# Mixer.net
KiCad netlist of a schematic drawn in EAGLE
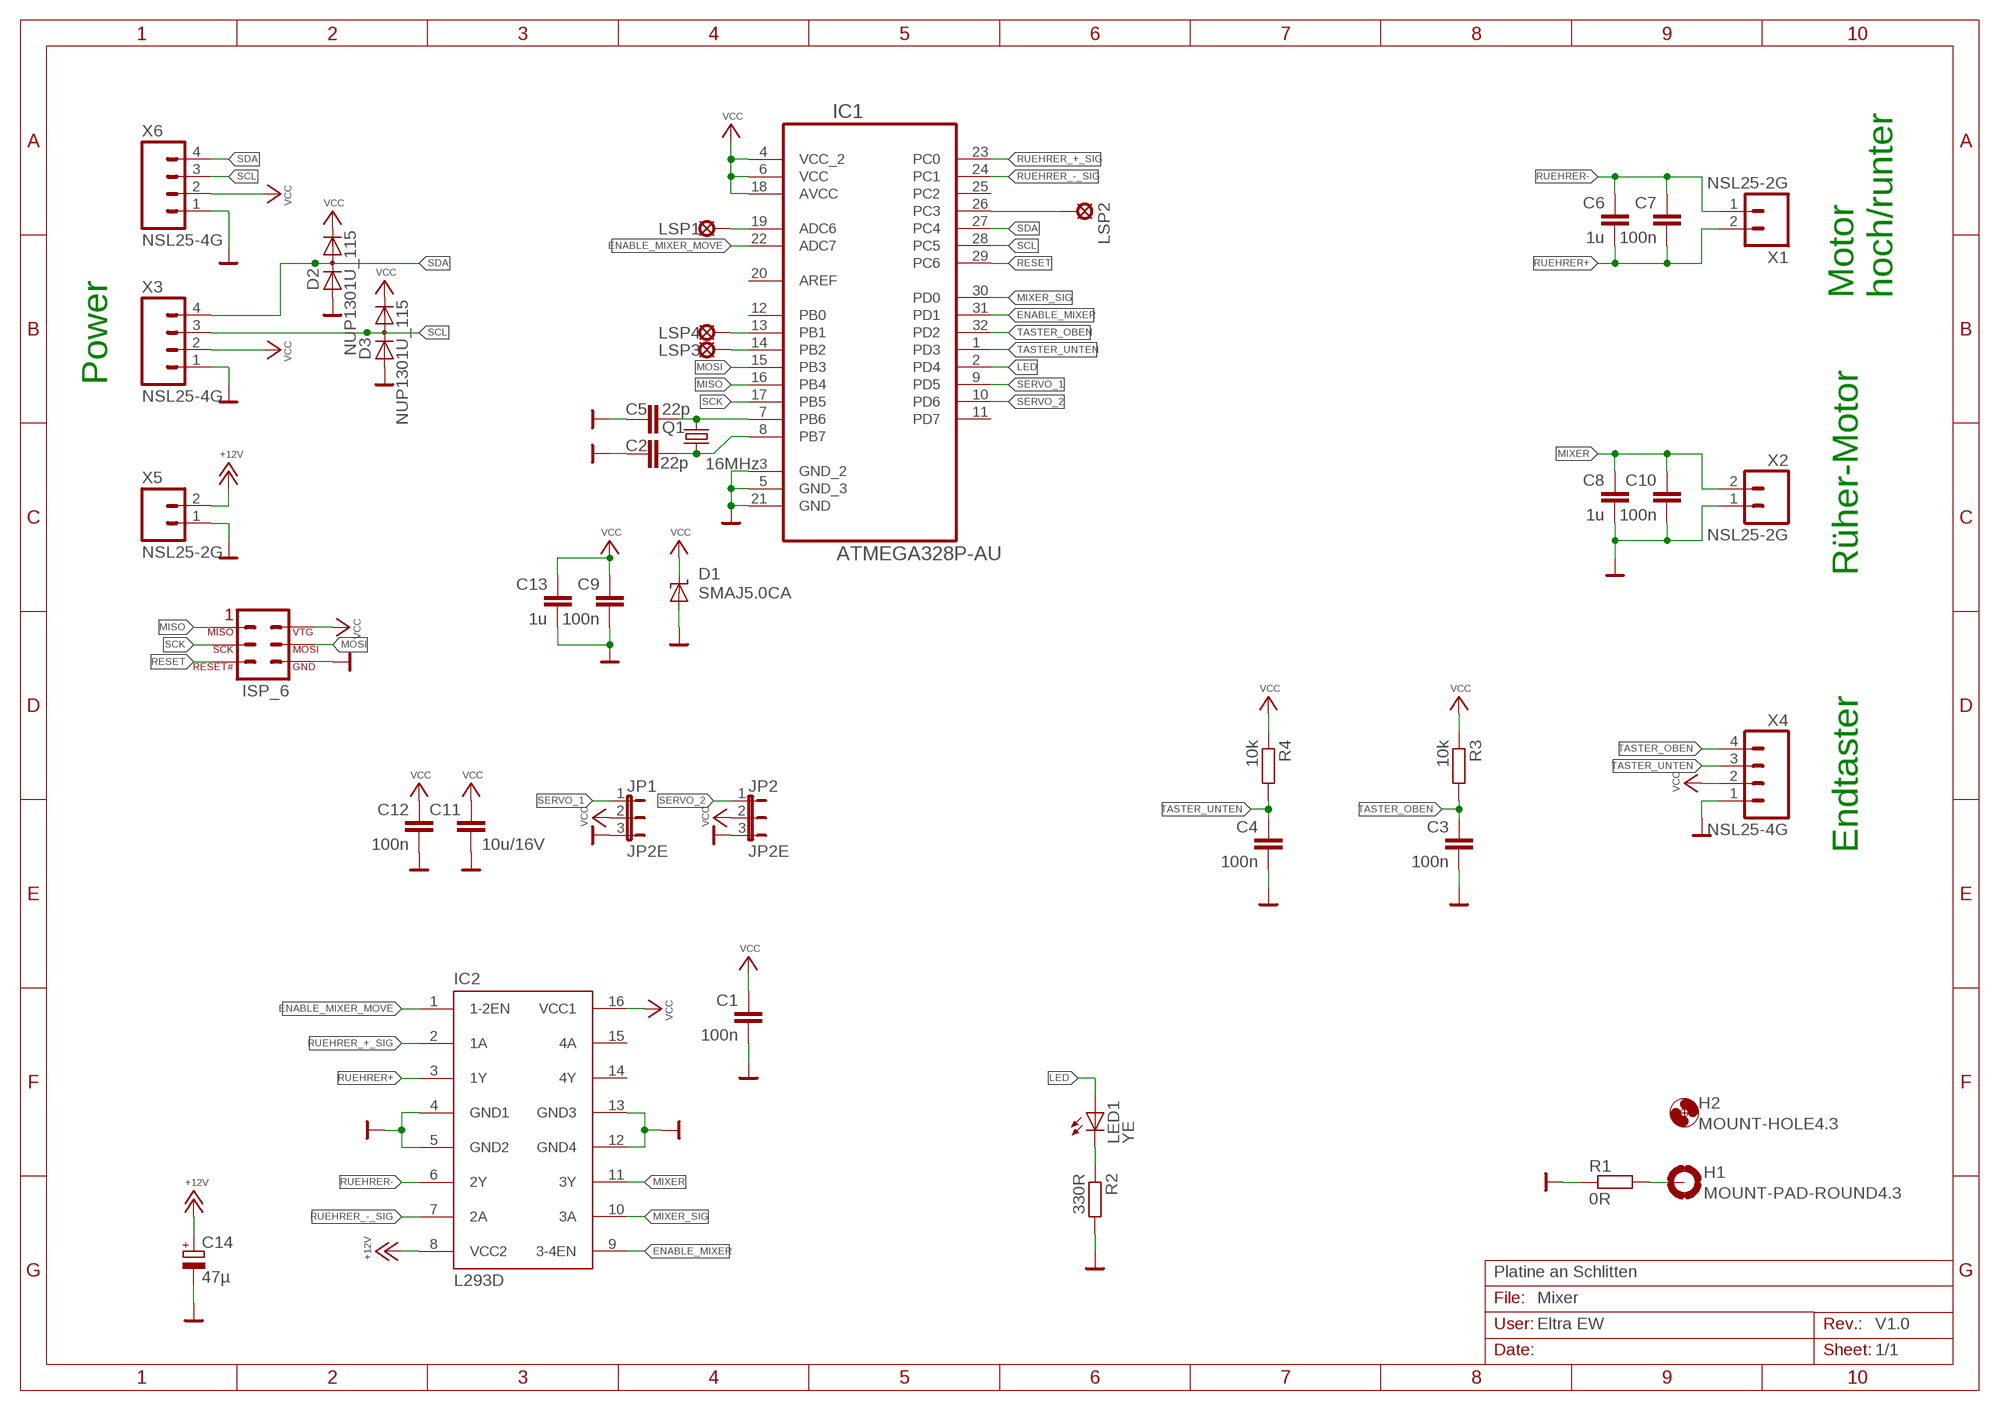
[diagram p0: schematic, sheet 1]

(export (version "E")
  (design (tool "Eeschema 10.0.6"))
  (components
    (comp (ref "C1")
      (value "100n")
      (footprint "eagle-import:0805CRH")
      (libsource (lib "eagle-import") (part "C-EUC0805CRH"))
    )
    (comp (ref "C2")
      (value "22p")
      (footprint "eagle-import:0805CRH")
      (libsource (lib "eagle-import") (part "C-EUC0805CRH"))
    )
    (comp (ref "C3")
      (value "100n")
      (footprint "eagle-import:0805CRH")
      (libsource (lib "eagle-import") (part "C-EUC0805CRH"))
    )
    (comp (ref "C4")
      (value "100n")
      (footprint "eagle-import:0805CRH")
      (libsource (lib "eagle-import") (part "C-EUC0805CRH"))
    )
    (comp (ref "C5")
      (value "22p")
      (footprint "eagle-import:0805CRH")
      (libsource (lib "eagle-import") (part "C-EUC0805CRH"))
    )
    (comp (ref "C6")
      (value "1u")
      (footprint "eagle-import:0805CRH")
      (libsource (lib "eagle-import") (part "C-EUC0805CRH"))
    )
    (comp (ref "C7")
      (value "100n")
      (footprint "eagle-import:0805CRH")
      (libsource (lib "eagle-import") (part "C-EUC0805CRH"))
    )
    (comp (ref "C8")
      (value "1u")
      (footprint "eagle-import:0805CRH")
      (libsource (lib "eagle-import") (part "C-EUC0805CRH"))
    )
    (comp (ref "C9")
      (value "100n")
      (footprint "eagle-import:0805CRH")
      (libsource (lib "eagle-import") (part "C-EUC0805CRH"))
    )
    (comp (ref "C10")
      (value "100n")
      (footprint "eagle-import:0805CRH")
      (libsource (lib "eagle-import") (part "C-EUC0805CRH"))
    )
    (comp (ref "C11")
      (value "10u/16V")
      (footprint "eagle-import:0805CRH")
      (libsource (lib "eagle-import") (part "C-EUC0805CRH"))
    )
    (comp (ref "C12")
      (value "100n")
      (footprint "eagle-import:0805CRH")
      (libsource (lib "eagle-import") (part "C-EUC0805CRH"))
    )
    (comp (ref "C13")
      (value "1u")
      (footprint "eagle-import:0805CRH")
      (libsource (lib "eagle-import") (part "C-EUC0805CRH"))
    )
    (comp (ref "C14")
      (value "47µ")
      (footprint "eagle-import:153CLV-0405")
      (libsource (lib "eagle-import") (part "CPOL-EU153CLV-0405"))
    )
    (comp (ref "D1")
      (value "SMAJ5.0CA")
      (footprint "eagle-import:SMA-DO214AC")
      (libsource (lib "eagle-import") (part "SMAJ"))
    )
    (comp (ref "D2")
      (value "NUP1301U_115")
      (footprint "eagle-import:SOT323-3")
      (libsource (lib "eagle-import") (part "NUP1301U_115"))
    )
    (comp (ref "D3")
      (value "NUP1301U_115")
      (footprint "eagle-import:SOT323-3")
      (libsource (lib "eagle-import") (part "NUP1301U_115"))
    )
    (comp (ref "H1")
      (value "MOUNT-PAD-ROUND4.3")
      (footprint "eagle-import:4,3-PAD")
      (libsource (lib "eagle-import") (part "MOUNT-PAD-ROUND4.3"))
    )
    (comp (ref "H2")
      (value "MOUNT-HOLE4.3")
      (footprint "eagle-import:4,3")
      (libsource (lib "eagle-import") (part "MOUNT-HOLE4.3"))
    )
    (comp (ref "IC1")
      (value "ATMEGA328P-AU")
      (footprint "eagle-import:QFP80P900X900X120-32N")
      (libsource (lib "eagle-import") (part "ATMEGA328P-AU"))
    )
    (comp (ref "IC2")
      (value "L293D")
      (footprint "eagle-import:DIL16")
      (libsource (lib "eagle-import") (part "L293D"))
    )
    (comp (ref "JP1")
      (value "JP2E")
      (footprint "eagle-import:JP2")
      (libsource (lib "eagle-import") (part "JP2E"))
    )
    (comp (ref "JP2")
      (value "JP2E")
      (footprint "eagle-import:JP2")
      (libsource (lib "eagle-import") (part "JP2E"))
    )
    (comp (ref "LED1")
      (value "YE")
      (footprint "eagle-import:CHIPLED_0805")
      (libsource (lib "eagle-import") (part "LEDCHIPLED_0805"))
    )
    (comp (ref "LSP1")
      (value "LSP06")
      (footprint "eagle-import:LSP06")
      (libsource (lib "eagle-import") (part "LSP06"))
    )
    (comp (ref "LSP2")
      (value "LSP06")
      (footprint "eagle-import:LSP06")
      (libsource (lib "eagle-import") (part "LSP06"))
    )
    (comp (ref "LSP3")
      (value "LSP06")
      (footprint "eagle-import:LSP06")
      (libsource (lib "eagle-import") (part "LSP06"))
    )
    (comp (ref "LSP4")
      (value "LSP06")
      (footprint "eagle-import:LSP06")
      (libsource (lib "eagle-import") (part "LSP06"))
    )
    (comp (ref "Q1")
      (value "16MHz")
      (footprint "eagle-import:HC49UP")
      (libsource (lib "eagle-import") (part "CRYSTALHC49UP"))
    )
    (comp (ref "R1")
      (value "0R")
      (footprint "eagle-import:0805CRH")
      (libsource (lib "eagle-import") (part "R-EU_R0805CRH"))
    )
    (comp (ref "R2")
      (value "330R")
      (footprint "eagle-import:0805CRH")
      (libsource (lib "eagle-import") (part "R-EU_R0805CRH"))
    )
    (comp (ref "R3")
      (value "10k")
      (footprint "eagle-import:0805CRH")
      (libsource (lib "eagle-import") (part "R-EU_R0805CRH"))
    )
    (comp (ref "R4")
      (value "10k")
      (footprint "eagle-import:0805CRH")
      (libsource (lib "eagle-import") (part "R-EU_R0805CRH"))
    )
    (comp (ref "SV1")
      (value "ATMEL_ISP_6")
      (footprint "eagle-import:ML6")
      (libsource (lib "eagle-import") (part "ATMEL_ISP_6"))
    )
    (comp (ref "X1")
      (value "NSL25-2G")
      (footprint "eagle-import:NSL25-2G")
      (libsource (lib "eagle-import") (part "NSL25-2G"))
    )
    (comp (ref "X2")
      (value "NSL25-2G")
      (footprint "eagle-import:NSL25-2G")
      (libsource (lib "eagle-import") (part "NSL25-2G"))
    )
    (comp (ref "X3")
      (value "NSL25-4G")
      (footprint "eagle-import:NSL25-4G")
      (libsource (lib "eagle-import") (part "NSL25-4G"))
    )
    (comp (ref "X4")
      (value "NSL25-4G")
      (footprint "eagle-import:NSL25-4G")
      (libsource (lib "eagle-import") (part "NSL25-4G"))
    )
    (comp (ref "X5")
      (value "NSL25-2G")
      (footprint "eagle-import:NSL25-2G")
      (libsource (lib "eagle-import") (part "NSL25-2G"))
    )
    (comp (ref "X6")
      (value "NSL25-4G")
      (footprint "eagle-import:NSL25-4G")
      (libsource (lib "eagle-import") (part "NSL25-4G"))
    )
  )
  (nets
    (net (code "1") (name "+12V") (class "Default")
      (node (ref "C14") (pin "+") (pinfunction "+_+") (pintype "passive"))
      (node (ref "IC2") (pin "8") (pinfunction "VCC2_8") (pintype "power_in"))
      (node (ref "X5") (pin "2") (pinfunction "2_2") (pintype "passive"))
    )
    (net (code "2") (name "ENABLE_MIXER") (class "Default")
      (node (ref "IC1") (pin "31") (pinfunction "PD1_31") (pintype "bidirectional"))
      (node (ref "IC2") (pin "9") (pinfunction "3-4EN_9") (pintype "input"))
    )
    (net (code "3") (name "ENABLE_MIXER_MOVE") (class "Default")
      (node (ref "IC1") (pin "22") (pinfunction "ADC7_22") (pintype "input"))
      (node (ref "IC2") (pin "1") (pinfunction "1-2EN_1") (pintype "input"))
    )
    (net (code "4") (name "GND") (class "Default")
      (node (ref "C1") (pin "2") (pinfunction "2_2") (pintype "passive"))
      (node (ref "C10") (pin "2") (pinfunction "2_2") (pintype "passive"))
      (node (ref "C11") (pin "2") (pinfunction "2_2") (pintype "passive"))
      (node (ref "C12") (pin "2") (pinfunction "2_2") (pintype "passive"))
      (node (ref "C13") (pin "2") (pinfunction "2_2") (pintype "passive"))
      (node (ref "C14") (pin "-") (pinfunction "-_-") (pintype "passive"))
      (node (ref "C2") (pin "1") (pinfunction "1_1") (pintype "passive"))
      (node (ref "C3") (pin "2") (pinfunction "2_2") (pintype "passive"))
      (node (ref "C4") (pin "2") (pinfunction "2_2") (pintype "passive"))
      (node (ref "C5") (pin "1") (pinfunction "1_1") (pintype "passive"))
      (node (ref "C8") (pin "2") (pinfunction "2_2") (pintype "passive"))
      (node (ref "C9") (pin "2") (pinfunction "2_2") (pintype "passive"))
      (node (ref "D1") (pin "A") (pinfunction "A_A") (pintype "passive"))
      (node (ref "D2") (pin "1") (pinfunction "1_1") (pintype "passive"))
      (node (ref "D3") (pin "1") (pinfunction "1_1") (pintype "passive"))
      (node (ref "IC1") (pin "21") (pinfunction "GND_21") (pintype "passive"))
      (node (ref "IC1") (pin "3") (pinfunction "GND_2_3") (pintype "passive"))
      (node (ref "IC1") (pin "5") (pinfunction "GND_3_5") (pintype "passive"))
      (node (ref "IC2") (pin "12") (pinfunction "GND4_12") (pintype "power_in"))
      (node (ref "IC2") (pin "13") (pinfunction "GND3_13") (pintype "power_in"))
      (node (ref "IC2") (pin "4") (pinfunction "GND1_4") (pintype "power_in"))
      (node (ref "IC2") (pin "5") (pinfunction "GND2_5") (pintype "power_in"))
      (node (ref "JP1") (pin "3") (pinfunction "3_3") (pintype "passive"))
      (node (ref "JP2") (pin "3") (pinfunction "3_3") (pintype "passive"))
      (node (ref "R1") (pin "1") (pinfunction "1_1") (pintype "passive"))
      (node (ref "R2") (pin "2") (pinfunction "2_2") (pintype "passive"))
      (node (ref "SV1") (pin "6") (pinfunction "6_6") (pintype "passive"))
      (node (ref "X2") (pin "1") (pinfunction "1_1") (pintype "passive"))
      (node (ref "X3") (pin "1") (pinfunction "1_1") (pintype "passive"))
      (node (ref "X4") (pin "1") (pinfunction "1_1") (pintype "passive"))
      (node (ref "X5") (pin "1") (pinfunction "1_1") (pintype "passive"))
      (node (ref "X6") (pin "1") (pinfunction "1_1") (pintype "passive"))
    )
    (net (code "5") (name "LED") (class "Default")
      (node (ref "IC1") (pin "2") (pinfunction "PD4_2") (pintype "bidirectional"))
      (node (ref "LED1") (pin "A") (pinfunction "A_A") (pintype "passive"))
    )
    (net (code "6") (name "MISO") (class "Default")
      (node (ref "IC1") (pin "16") (pinfunction "PB4_16") (pintype "bidirectional"))
      (node (ref "SV1") (pin "1") (pinfunction "1_1") (pintype "passive"))
    )
    (net (code "7") (name "MIXER") (class "Default")
      (node (ref "C10") (pin "1") (pinfunction "1_1") (pintype "passive"))
      (node (ref "C8") (pin "1") (pinfunction "1_1") (pintype "passive"))
      (node (ref "IC2") (pin "11") (pinfunction "3Y_11") (pintype "output"))
      (node (ref "X2") (pin "2") (pinfunction "2_2") (pintype "passive"))
    )
    (net (code "8") (name "MIXER_SIG") (class "Default")
      (node (ref "IC1") (pin "30") (pinfunction "PD0_30") (pintype "bidirectional"))
      (node (ref "IC2") (pin "10") (pinfunction "3A_10") (pintype "input"))
    )
    (net (code "9") (name "MOSI") (class "Default")
      (node (ref "IC1") (pin "15") (pinfunction "PB3_15") (pintype "bidirectional"))
      (node (ref "SV1") (pin "4") (pinfunction "4_4") (pintype "passive"))
    )
    (net (code "10") (name "Net-(H1-MOUNT)") (class "Default")
      (node (ref "H1") (pin "B4,3") (pinfunction "MOUNT_B4,3") (pintype "passive"))
      (node (ref "R1") (pin "2") (pinfunction "2_2") (pintype "passive"))
    )
    (net (code "11") (name "Net-(IC1-ADC6)") (class "Default")
      (node (ref "IC1") (pin "19") (pinfunction "ADC6_19") (pintype "input"))
      (node (ref "LSP1") (pin "MP") (pinfunction "MP_MP") (pintype "passive"))
    )
    (net (code "12") (name "Net-(IC1-PB1)") (class "Default")
      (node (ref "IC1") (pin "13") (pinfunction "PB1_13") (pintype "bidirectional"))
      (node (ref "LSP4") (pin "MP") (pinfunction "MP_MP") (pintype "passive"))
    )
    (net (code "13") (name "Net-(IC1-PB2)") (class "Default")
      (node (ref "IC1") (pin "14") (pinfunction "PB2_14") (pintype "bidirectional"))
      (node (ref "LSP3") (pin "MP") (pinfunction "MP_MP") (pintype "passive"))
    )
    (net (code "14") (name "Net-(IC1-PB6)") (class "Default")
      (node (ref "C5") (pin "2") (pinfunction "2_2") (pintype "passive"))
      (node (ref "IC1") (pin "7") (pinfunction "PB6_7") (pintype "bidirectional"))
      (node (ref "Q1") (pin "2") (pinfunction "2_2") (pintype "passive"))
    )
    (net (code "15") (name "Net-(IC1-PB7)") (class "Default")
      (node (ref "C2") (pin "2") (pinfunction "2_2") (pintype "passive"))
      (node (ref "IC1") (pin "8") (pinfunction "PB7_8") (pintype "bidirectional"))
      (node (ref "Q1") (pin "1") (pinfunction "1_1") (pintype "passive"))
    )
    (net (code "16") (name "Net-(IC1-PC3)") (class "Default")
      (node (ref "IC1") (pin "26") (pinfunction "PC3_26") (pintype "bidirectional"))
      (node (ref "LSP2") (pin "MP") (pinfunction "MP_MP") (pintype "passive"))
    )
    (net (code "17") (name "Net-(LED1-PadC)") (class "Default")
      (node (ref "LED1") (pin "C") (pinfunction "C_C") (pintype "passive"))
      (node (ref "R2") (pin "1") (pinfunction "1_1") (pintype "passive"))
    )
    (net (code "18") (name "RESET") (class "Default")
      (node (ref "IC1") (pin "29") (pinfunction "PC6_29") (pintype "bidirectional"))
      (node (ref "SV1") (pin "5") (pinfunction "5_5") (pintype "passive"))
    )
    (net (code "19") (name "RUEHRER+") (class "Default")
      (node (ref "C6") (pin "2") (pinfunction "2_2") (pintype "passive"))
      (node (ref "C7") (pin "2") (pinfunction "2_2") (pintype "passive"))
      (node (ref "IC2") (pin "3") (pinfunction "1Y_3") (pintype "output"))
      (node (ref "X1") (pin "2") (pinfunction "2_2") (pintype "passive"))
    )
    (net (code "20") (name "RUEHRER-") (class "Default")
      (node (ref "C6") (pin "1") (pinfunction "1_1") (pintype "passive"))
      (node (ref "C7") (pin "1") (pinfunction "1_1") (pintype "passive"))
      (node (ref "IC2") (pin "6") (pinfunction "2Y_6") (pintype "output"))
      (node (ref "X1") (pin "1") (pinfunction "1_1") (pintype "passive"))
    )
    (net (code "21") (name "RUEHRER_+_SIG") (class "Default")
      (node (ref "IC1") (pin "23") (pinfunction "PC0_23") (pintype "bidirectional"))
      (node (ref "IC2") (pin "2") (pinfunction "1A_2") (pintype "input"))
    )
    (net (code "22") (name "RUEHRER_-_SIG") (class "Default")
      (node (ref "IC1") (pin "24") (pinfunction "PC1_24") (pintype "bidirectional"))
      (node (ref "IC2") (pin "7") (pinfunction "2A_7") (pintype "input"))
    )
    (net (code "23") (name "SCK") (class "Default")
      (node (ref "IC1") (pin "17") (pinfunction "PB5_17") (pintype "bidirectional"))
      (node (ref "SV1") (pin "3") (pinfunction "3_3") (pintype "passive"))
    )
    (net (code "24") (name "SCL") (class "Default")
      (node (ref "D3") (pin "3") (pinfunction "3_3") (pintype "passive"))
      (node (ref "IC1") (pin "28") (pinfunction "PC5_28") (pintype "bidirectional"))
      (node (ref "X3") (pin "3") (pinfunction "3_3") (pintype "passive"))
      (node (ref "X6") (pin "3") (pinfunction "3_3") (pintype "passive"))
    )
    (net (code "25") (name "SDA") (class "Default")
      (node (ref "D2") (pin "3") (pinfunction "3_3") (pintype "passive"))
      (node (ref "IC1") (pin "27") (pinfunction "PC4_27") (pintype "bidirectional"))
      (node (ref "X3") (pin "4") (pinfunction "4_4") (pintype "passive"))
      (node (ref "X6") (pin "4") (pinfunction "4_4") (pintype "passive"))
    )
    (net (code "26") (name "SERVO_1") (class "Default")
      (node (ref "IC1") (pin "9") (pinfunction "PD5_9") (pintype "bidirectional"))
      (node (ref "JP1") (pin "1") (pinfunction "1_1") (pintype "passive"))
    )
    (net (code "27") (name "SERVO_2") (class "Default")
      (node (ref "IC1") (pin "10") (pinfunction "PD6_10") (pintype "bidirectional"))
      (node (ref "JP2") (pin "1") (pinfunction "1_1") (pintype "passive"))
    )
    (net (code "28") (name "TASTER_OBEN") (class "Default")
      (node (ref "C3") (pin "1") (pinfunction "1_1") (pintype "passive"))
      (node (ref "IC1") (pin "32") (pinfunction "PD2_32") (pintype "bidirectional"))
      (node (ref "R3") (pin "2") (pinfunction "2_2") (pintype "passive"))
      (node (ref "X4") (pin "4") (pinfunction "4_4") (pintype "passive"))
    )
    (net (code "29") (name "TASTER_UNTEN") (class "Default")
      (node (ref "C4") (pin "1") (pinfunction "1_1") (pintype "passive"))
      (node (ref "IC1") (pin "1") (pinfunction "PD3_1") (pintype "bidirectional"))
      (node (ref "R4") (pin "2") (pinfunction "2_2") (pintype "passive"))
      (node (ref "X4") (pin "3") (pinfunction "3_3") (pintype "passive"))
    )
    (net (code "30") (name "VCC") (class "Default")
      (node (ref "C1") (pin "1") (pinfunction "1_1") (pintype "passive"))
      (node (ref "C11") (pin "1") (pinfunction "1_1") (pintype "passive"))
      (node (ref "C12") (pin "1") (pinfunction "1_1") (pintype "passive"))
      (node (ref "C13") (pin "1") (pinfunction "1_1") (pintype "passive"))
      (node (ref "C9") (pin "1") (pinfunction "1_1") (pintype "passive"))
      (node (ref "D1") (pin "K") (pinfunction "C_K") (pintype "passive"))
      (node (ref "D2") (pin "2") (pinfunction "2_2") (pintype "passive"))
      (node (ref "D3") (pin "2") (pinfunction "2_2") (pintype "passive"))
      (node (ref "IC1") (pin "18") (pinfunction "AVCC_18") (pintype "power_in"))
      (node (ref "IC1") (pin "4") (pinfunction "VCC_2_4") (pintype "power_in"))
      (node (ref "IC1") (pin "6") (pinfunction "VCC_6") (pintype "power_in"))
      (node (ref "IC2") (pin "16") (pinfunction "VCC1_16") (pintype "power_in"))
      (node (ref "JP1") (pin "2") (pinfunction "2_2") (pintype "passive"))
      (node (ref "JP2") (pin "2") (pinfunction "2_2") (pintype "passive"))
      (node (ref "R3") (pin "1") (pinfunction "1_1") (pintype "passive"))
      (node (ref "R4") (pin "1") (pinfunction "1_1") (pintype "passive"))
      (node (ref "SV1") (pin "2") (pinfunction "2_2") (pintype "passive"))
      (node (ref "X3") (pin "2") (pinfunction "2_2") (pintype "passive"))
      (node (ref "X4") (pin "2") (pinfunction "2_2") (pintype "passive"))
      (node (ref "X6") (pin "2") (pinfunction "2_2") (pintype "passive"))
    )
    (net (code "31") (name "unconnected-(IC1-AREF-Pad20)") (class "Default")
      (node (ref "IC1") (pin "20") (pinfunction "AREF_20") (pintype "input"))
    )
    (net (code "32") (name "unconnected-(IC1-PB0-Pad12)") (class "Default")
      (node (ref "IC1") (pin "12") (pinfunction "PB0_12") (pintype "bidirectional"))
    )
    (net (code "33") (name "unconnected-(IC1-PC2-Pad25)") (class "Default")
      (node (ref "IC1") (pin "25") (pinfunction "PC2_25") (pintype "bidirectional"))
    )
    (net (code "34") (name "unconnected-(IC1-PD7-Pad11)") (class "Default")
      (node (ref "IC1") (pin "11") (pinfunction "PD7_11") (pintype "bidirectional"))
    )
    (net (code "35") (name "unconnected-(IC2-4A-Pad15)") (class "Default")
      (node (ref "IC2") (pin "15") (pinfunction "4A_15") (pintype "input"))
    )
    (net (code "36") (name "unconnected-(IC2-4Y-Pad14)") (class "Default")
      (node (ref "IC2") (pin "14") (pinfunction "4Y_14") (pintype "output"))
    )
  )
)
